# HW1_2.net
KiCad netlist of a schematic drawn in EasyEDA
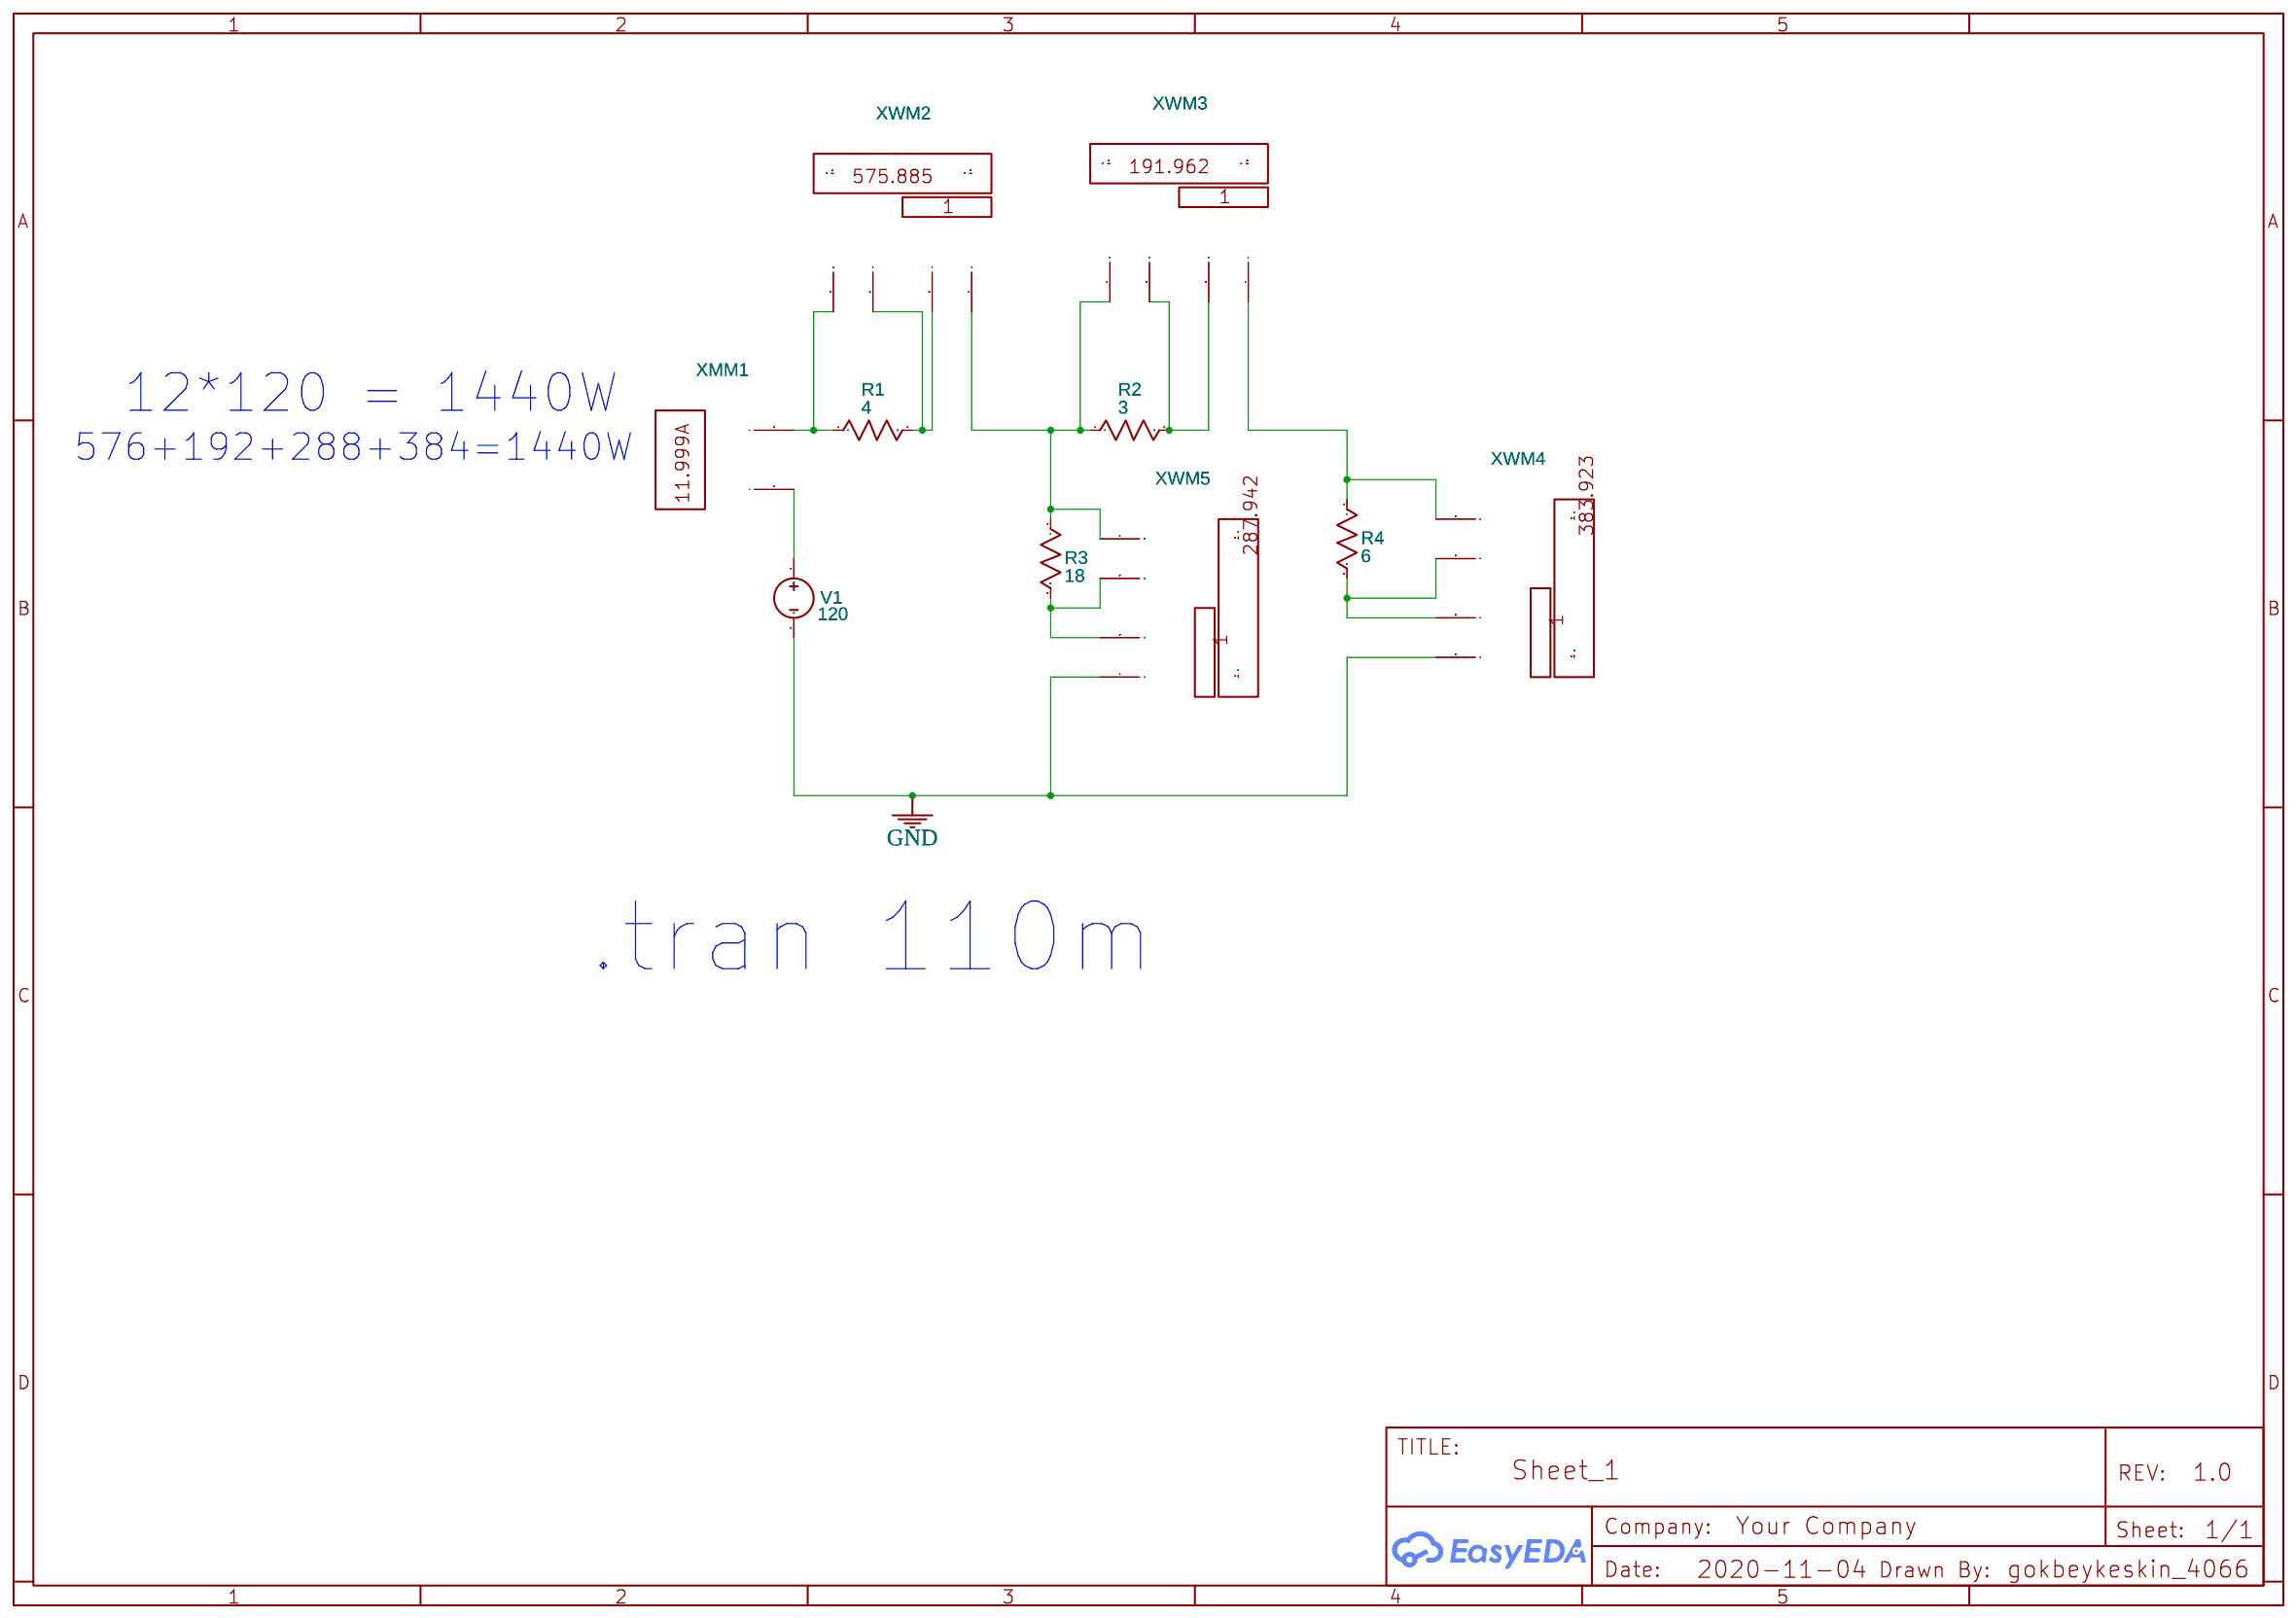
[diagram p0: schematic sheet]

(export (version "E")
  (design (tool "Eeschema 10.0.6"))
  (components
    (comp (ref "R1") (value "4") (libsource (lib "") (part "Resistor_US_1")))
    (comp (ref "R2") (value "3") (libsource (lib "") (part "Resistor_US_1")))
    (comp (ref "R3") (value "18") (libsource (lib "") (part "Resistor_US")))
    (comp (ref "R4") (value "6") (libsource (lib "") (part "Resistor_US")))
    (comp (ref "V1") (value "120") (libsource (lib "") (part "VDC")))
    (comp (ref "XMM1") (value "Multimeter") (libsource (lib "") (part "MULTIMETER")))
    (comp (ref "XWM2") (value "Wattmeter") (libsource (lib "") (part "WATTMETER_1")))
    (comp (ref "XWM3") (value "Wattmeter") (libsource (lib "") (part "WATTMETER")))
    (comp (ref "XWM4") (value "Wattmeter") (libsource (lib "") (part "WATTMETER_3")))
    (comp (ref "XWM5") (value "Wattmeter") (libsource (lib "") (part "WATTMETER_2")))
  )
  (nets
    (net (code "1") (name "GND") (class "Default")
      (node (ref "V1") (pin "2") (pinfunction "2_2") (pintype "unspecified"))
      (node (ref "XWM4") (pin "4") (pinfunction "I-_4") (pintype "unspecified"))
      (node (ref "XWM5") (pin "4") (pinfunction "I-_4") (pintype "unspecified"))
    )
    (net (code "2") (name "Net-(XMM1-+)") (class "Default")
      (node (ref "V1") (pin "1") (pinfunction "1_1") (pintype "unspecified"))
      (node (ref "XMM1") (pin "1") (pinfunction "+_1") (pintype "unspecified"))
    )
    (net (code "3") (name "Net-(XMM1-I)") (class "Default")
      (node (ref "R1") (pin "1") (pinfunction "1_1") (pintype "unspecified"))
      (node (ref "XMM1") (pin "2") (pinfunction "I_2") (pintype "unspecified"))
      (node (ref "XWM2") (pin "1") (pinfunction "V+_1") (pintype "unspecified"))
    )
    (net (code "4") (name "Net-(XWM2-I+)") (class "Default")
      (node (ref "R1") (pin "2") (pinfunction "2_2") (pintype "unspecified"))
      (node (ref "XWM2") (pin "2") (pinfunction "V-_2") (pintype "unspecified"))
      (node (ref "XWM2") (pin "3") (pinfunction "I+_3") (pintype "unspecified"))
    )
    (net (code "5") (name "Net-(XWM2-I-)") (class "Default")
      (node (ref "R2") (pin "1") (pinfunction "1_1") (pintype "unspecified"))
      (node (ref "R3") (pin "1") (pinfunction "1_1") (pintype "unspecified"))
      (node (ref "XWM2") (pin "4") (pinfunction "I-_4") (pintype "unspecified"))
      (node (ref "XWM3") (pin "1") (pinfunction "V+_1") (pintype "unspecified"))
      (node (ref "XWM5") (pin "1") (pinfunction "V+_1") (pintype "unspecified"))
    )
    (net (code "6") (name "Net-(XWM3-I+)") (class "Default")
      (node (ref "R2") (pin "2") (pinfunction "2_2") (pintype "unspecified"))
      (node (ref "XWM3") (pin "2") (pinfunction "V-_2") (pintype "unspecified"))
      (node (ref "XWM3") (pin "3") (pinfunction "I+_3") (pintype "unspecified"))
    )
    (net (code "7") (name "Net-(XWM3-I-)") (class "Default")
      (node (ref "R4") (pin "1") (pinfunction "1_1") (pintype "unspecified"))
      (node (ref "XWM3") (pin "4") (pinfunction "I-_4") (pintype "unspecified"))
      (node (ref "XWM4") (pin "1") (pinfunction "V+_1") (pintype "unspecified"))
    )
    (net (code "8") (name "Net-(XWM4-I+)") (class "Default")
      (node (ref "R4") (pin "2") (pinfunction "2_2") (pintype "unspecified"))
      (node (ref "XWM4") (pin "2") (pinfunction "V-_2") (pintype "unspecified"))
      (node (ref "XWM4") (pin "3") (pinfunction "I+_3") (pintype "unspecified"))
    )
    (net (code "9") (name "Net-(XWM5-I+)") (class "Default")
      (node (ref "R3") (pin "2") (pinfunction "2_2") (pintype "unspecified"))
      (node (ref "XWM5") (pin "2") (pinfunction "V-_2") (pintype "unspecified"))
      (node (ref "XWM5") (pin "3") (pinfunction "I+_3") (pintype "unspecified"))
    )
    (net (code "10") (name "unconnected-(XWM2-PadP)") (class "Default")
      (node (ref "XWM2") (pin "P") (pinfunction "P_P") (pintype "unspecified"))
    )
    (net (code "11") (name "unconnected-(XWM2-PadPF)") (class "Default")
      (node (ref "XWM2") (pin "PF") (pinfunction "PF_PF") (pintype "unspecified"))
    )
    (net (code "12") (name "unconnected-(XWM3-PadP)") (class "Default")
      (node (ref "XWM3") (pin "P") (pinfunction "P_P") (pintype "unspecified"))
    )
    (net (code "13") (name "unconnected-(XWM3-PadPF)") (class "Default")
      (node (ref "XWM3") (pin "PF") (pinfunction "PF_PF") (pintype "unspecified"))
    )
    (net (code "14") (name "unconnected-(XWM4-PadP)") (class "Default")
      (node (ref "XWM4") (pin "P") (pinfunction "P_P") (pintype "unspecified"))
    )
    (net (code "15") (name "unconnected-(XWM4-PadPF)") (class "Default")
      (node (ref "XWM4") (pin "PF") (pinfunction "PF_PF") (pintype "unspecified"))
    )
    (net (code "16") (name "unconnected-(XWM5-PadP)") (class "Default")
      (node (ref "XWM5") (pin "P") (pinfunction "P_P") (pintype "unspecified"))
    )
    (net (code "17") (name "unconnected-(XWM5-PadPF)") (class "Default")
      (node (ref "XWM5") (pin "PF") (pinfunction "PF_PF") (pintype "unspecified"))
    )
  )
)
